# candle.net
KiCad netlist of a schematic drawn in EAGLE
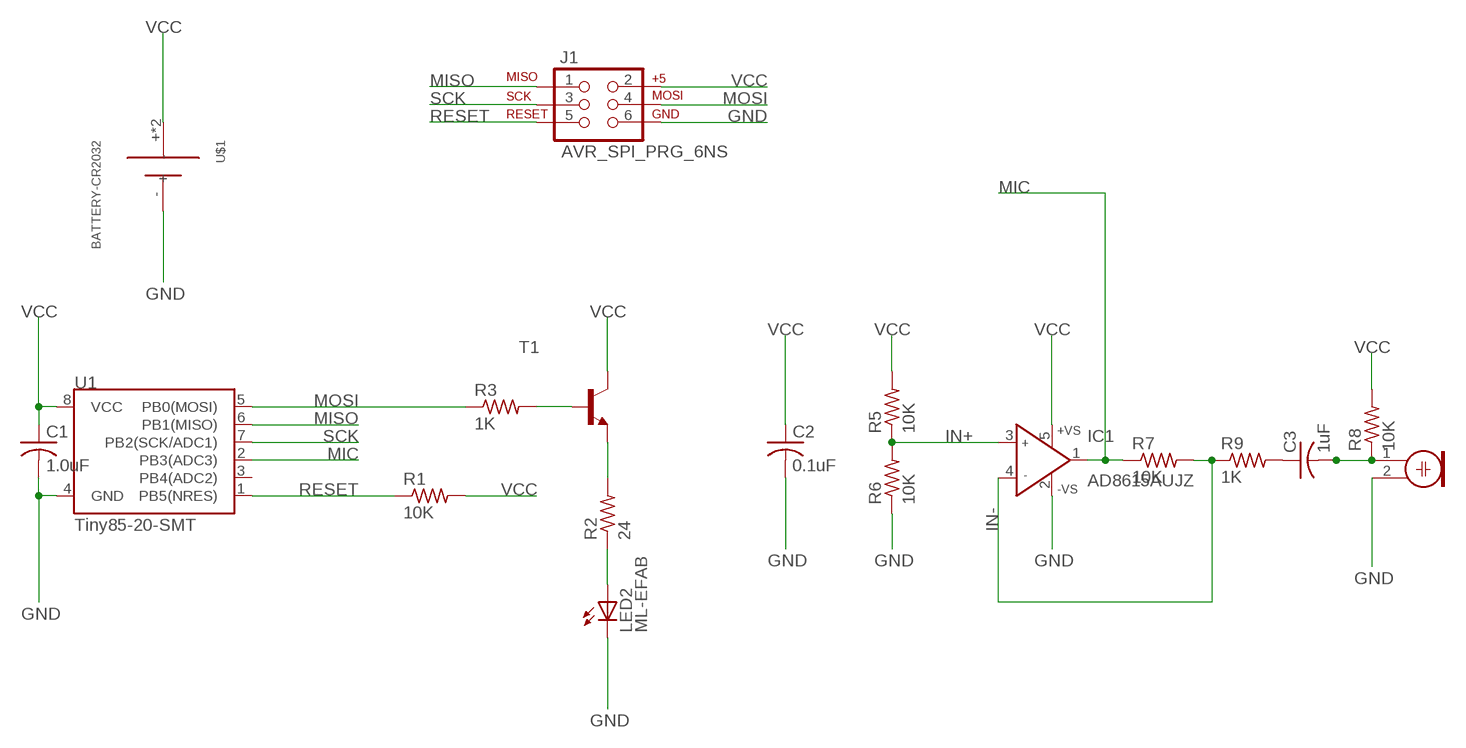
[diagram p0: schematic, sheet 1]

(export (version "E")
  (design (tool "Eeschema 10.0.6"))
  (components
    (comp (ref "C1")
      (value "1.0uF")
      (footprint "eagle-import:C1206")
      (libsource (lib "eagle-import") (part "C-USC1206"))
    )
    (comp (ref "C2")
      (value "0.1uF")
      (footprint "eagle-import:C1206")
      (libsource (lib "eagle-import") (part "C-USC1206"))
    )
    (comp (ref "C3")
      (value "1uF")
      (footprint "eagle-import:C1206")
      (libsource (lib "eagle-import") (part "C-USC1206"))
    )
    (comp (ref "IC1")
      (value "AD8615AUJZ")
      (footprint "eagle-import:SOT23-5")
      (fields (field (name "MF") "ALTERA CORPORATION") (field (name "MPN") "AD8614ARTZ-REEL7"))
      (libsource (lib "eagle-import") (part "AD8614RJ"))
    )
    (comp (ref "J1")
      (value "AVR_SPI_PRG_6NS")
      (footprint "eagle-import:2X3-NS")
      (libsource (lib "eagle-import") (part "AVR_SPI_PRG_6NS"))
    )
    (comp (ref "LED2")
      (value "ML-EFAB")
      (footprint "eagle-import:ML-E-FAB")
      (libsource (lib "eagle-import") (part "ML-EFAB"))
    )
    (comp (ref "M1")
      (value "ELECTRETTH")
      (footprint "eagle-import:ELECTRET_6MM_TH")
      (libsource (lib "eagle-import") (part "ELECTRETTH"))
    )
    (comp (ref "R1")
      (value "10K")
      (footprint "eagle-import:R1206")
      (libsource (lib "eagle-import") (part "R-US_R1206"))
    )
    (comp (ref "R2")
      (value "24")
      (footprint "eagle-import:R1206")
      (libsource (lib "eagle-import") (part "R-US_R1206"))
    )
    (comp (ref "R3")
      (value "1K")
      (footprint "eagle-import:R1206")
      (libsource (lib "eagle-import") (part "R-US_R1206"))
    )
    (comp (ref "R5")
      (value "10K")
      (footprint "eagle-import:R1206")
      (libsource (lib "eagle-import") (part "R-US_R1206"))
    )
    (comp (ref "R6")
      (value "10K")
      (footprint "eagle-import:R1206")
      (libsource (lib "eagle-import") (part "R-US_R1206"))
    )
    (comp (ref "R7")
      (value "10K")
      (footprint "eagle-import:R1206")
      (libsource (lib "eagle-import") (part "R-US_R1206"))
    )
    (comp (ref "R8")
      (value "10K")
      (footprint "eagle-import:R1206")
      (libsource (lib "eagle-import") (part "R-US_R1206"))
    )
    (comp (ref "R9")
      (value "1K")
      (footprint "eagle-import:R1206")
      (libsource (lib "eagle-import") (part "R-US_R1206"))
    )
    (comp (ref "T1")
      (value "MMBT3904LT1-NPN-SOT23-BEC")
      (footprint "eagle-import:SOT23-BEC")
      (libsource (lib "eagle-import") (part "-NPN-SOT23-BECMMBT3904LT1"))
    )
    (comp (ref "U$1")
      (value "BATTERY-CR2032")
      (footprint "eagle-import:CR2032_TH")
      (libsource (lib "eagle-import") (part "BATTERY-CR2032"))
    )
    (comp (ref "U1")
      (value "Tiny85-20-SMT")
      (footprint "eagle-import:SO08-EIAJ")
      (libsource (lib "eagle-import") (part "ATTINY45TINY85-20-SMT"))
    )
  )
  (nets
    (net (code "1") (name "/GND") (class "Default")
      (node (ref "C1") (pin "2") (pinfunction "2_2") (pintype "passive"))
      (node (ref "C2") (pin "2") (pinfunction "2_2") (pintype "passive"))
      (node (ref "IC1") (pin "2") (pinfunction "-VS_2") (pintype "input"))
      (node (ref "J1") (pin "6") (pinfunction "6_6") (pintype "passive"))
      (node (ref "LED2") (pin "C@1") (pinfunction "C_C@1") (pintype "passive"))
      (node (ref "M1") (pin "2") (pinfunction "2_2") (pintype "passive"))
      (node (ref "R6") (pin "1") (pinfunction "1_1") (pintype "passive"))
      (node (ref "U$1") (pin "-") (pinfunction "-_-") (pintype "bidirectional"))
      (node (ref "U1") (pin "4") (pinfunction "GND_4") (pintype "bidirectional"))
    )
    (net (code "2") (name "/IN+") (class "Default")
      (node (ref "IC1") (pin "3") (pinfunction "IN+_3") (pintype "input"))
      (node (ref "R5") (pin "1") (pinfunction "1_1") (pintype "passive"))
      (node (ref "R6") (pin "2") (pinfunction "2_2") (pintype "passive"))
    )
    (net (code "3") (name "/IN-") (class "Default")
      (node (ref "IC1") (pin "4") (pinfunction "IN-_4") (pintype "input"))
      (node (ref "R7") (pin "2") (pinfunction "2_2") (pintype "passive"))
      (node (ref "R9") (pin "1") (pinfunction "1_1") (pintype "passive"))
    )
    (net (code "4") (name "/MIC") (class "Default")
      (node (ref "IC1") (pin "1") (pinfunction "OUT_1") (pintype "output"))
      (node (ref "R7") (pin "1") (pinfunction "1_1") (pintype "passive"))
      (node (ref "U1") (pin "2") (pinfunction "PB3(ADC3)_2") (pintype "bidirectional"))
    )
    (net (code "5") (name "/MISO") (class "Default")
      (node (ref "J1") (pin "1") (pinfunction "1_1") (pintype "passive"))
      (node (ref "U1") (pin "6") (pinfunction "PB1(MISO)_6") (pintype "bidirectional"))
    )
    (net (code "6") (name "/MOSI") (class "Default")
      (node (ref "J1") (pin "4") (pinfunction "4_4") (pintype "passive"))
      (node (ref "R3") (pin "1") (pinfunction "1_1") (pintype "passive"))
      (node (ref "U1") (pin "5") (pinfunction "PB0(MOSI)_5") (pintype "bidirectional"))
    )
    (net (code "7") (name "/RESET") (class "Default")
      (node (ref "J1") (pin "5") (pinfunction "5_5") (pintype "passive"))
      (node (ref "R1") (pin "1") (pinfunction "1_1") (pintype "passive"))
      (node (ref "U1") (pin "1") (pinfunction "PB5(NRES)_1") (pintype "bidirectional"))
    )
    (net (code "8") (name "/SCK") (class "Default")
      (node (ref "J1") (pin "3") (pinfunction "3_3") (pintype "passive"))
      (node (ref "U1") (pin "7") (pinfunction "PB2(SCK/ADC1)_7") (pintype "bidirectional"))
    )
    (net (code "9") (name "/VCC") (class "Default")
      (node (ref "C1") (pin "1") (pinfunction "1_1") (pintype "passive"))
      (node (ref "C2") (pin "1") (pinfunction "1_1") (pintype "passive"))
      (node (ref "IC1") (pin "5") (pinfunction "+VS_5") (pintype "input"))
      (node (ref "J1") (pin "2") (pinfunction "2_2") (pintype "passive"))
      (node (ref "R1") (pin "2") (pinfunction "2_2") (pintype "passive"))
      (node (ref "R5") (pin "2") (pinfunction "2_2") (pintype "passive"))
      (node (ref "R8") (pin "2") (pinfunction "2_2") (pintype "passive"))
      (node (ref "T1") (pin "C") (pinfunction "C_C") (pintype "passive"))
      (node (ref "U$1") (pin "+") (pinfunction "+_+") (pintype "bidirectional"))
      (node (ref "U$1") (pin "+'") (pinfunction "+_+'") (pintype "bidirectional"))
      (node (ref "U1") (pin "8") (pinfunction "VCC_8") (pintype "bidirectional"))
    )
    (net (code "10") (name "Net-(C3-Pad1)") (class "Default")
      (node (ref "C3") (pin "1") (pinfunction "1_1") (pintype "passive"))
      (node (ref "R9") (pin "2") (pinfunction "2_2") (pintype "passive"))
    )
    (net (code "11") (name "Net-(C3-Pad2)") (class "Default")
      (node (ref "C3") (pin "2") (pinfunction "2_2") (pintype "passive"))
      (node (ref "M1") (pin "1") (pinfunction "1_1") (pintype "passive"))
      (node (ref "R8") (pin "1") (pinfunction "1_1") (pintype "passive"))
    )
    (net (code "12") (name "Net-(LED2A-A-PadA@1)") (class "Default")
      (node (ref "LED2") (pin "A@1") (pinfunction "A_A@1") (pintype "passive"))
      (node (ref "R2") (pin "1") (pinfunction "1_1") (pintype "passive"))
    )
    (net (code "13") (name "Net-(R2-Pad2)") (class "Default")
      (node (ref "R2") (pin "2") (pinfunction "2_2") (pintype "passive"))
      (node (ref "T1") (pin "E") (pinfunction "E_E") (pintype "passive"))
    )
    (net (code "14") (name "Net-(R3-Pad2)") (class "Default")
      (node (ref "R3") (pin "2") (pinfunction "2_2") (pintype "passive"))
      (node (ref "T1") (pin "B") (pinfunction "B_B") (pintype "passive"))
    )
    (net (code "15") (name "unconnected-(LED2A-A-PadA@2)") (class "Default")
      (node (ref "LED2") (pin "A@2") (pinfunction "A_A@2") (pintype "passive"))
    )
    (net (code "16") (name "unconnected-(LED2A-C-PadC@2)") (class "Default")
      (node (ref "LED2") (pin "C@2") (pinfunction "C_C@2") (pintype "passive"))
    )
    (net (code "17") (name "unconnected-(U1-PB4(ADC2)-Pad3)") (class "Default")
      (node (ref "U1") (pin "3") (pinfunction "PB4(ADC2)_3") (pintype "bidirectional"))
    )
  )
)
